# rauchmelder.net
KiCad netlist of a schematic drawn in EAGLE
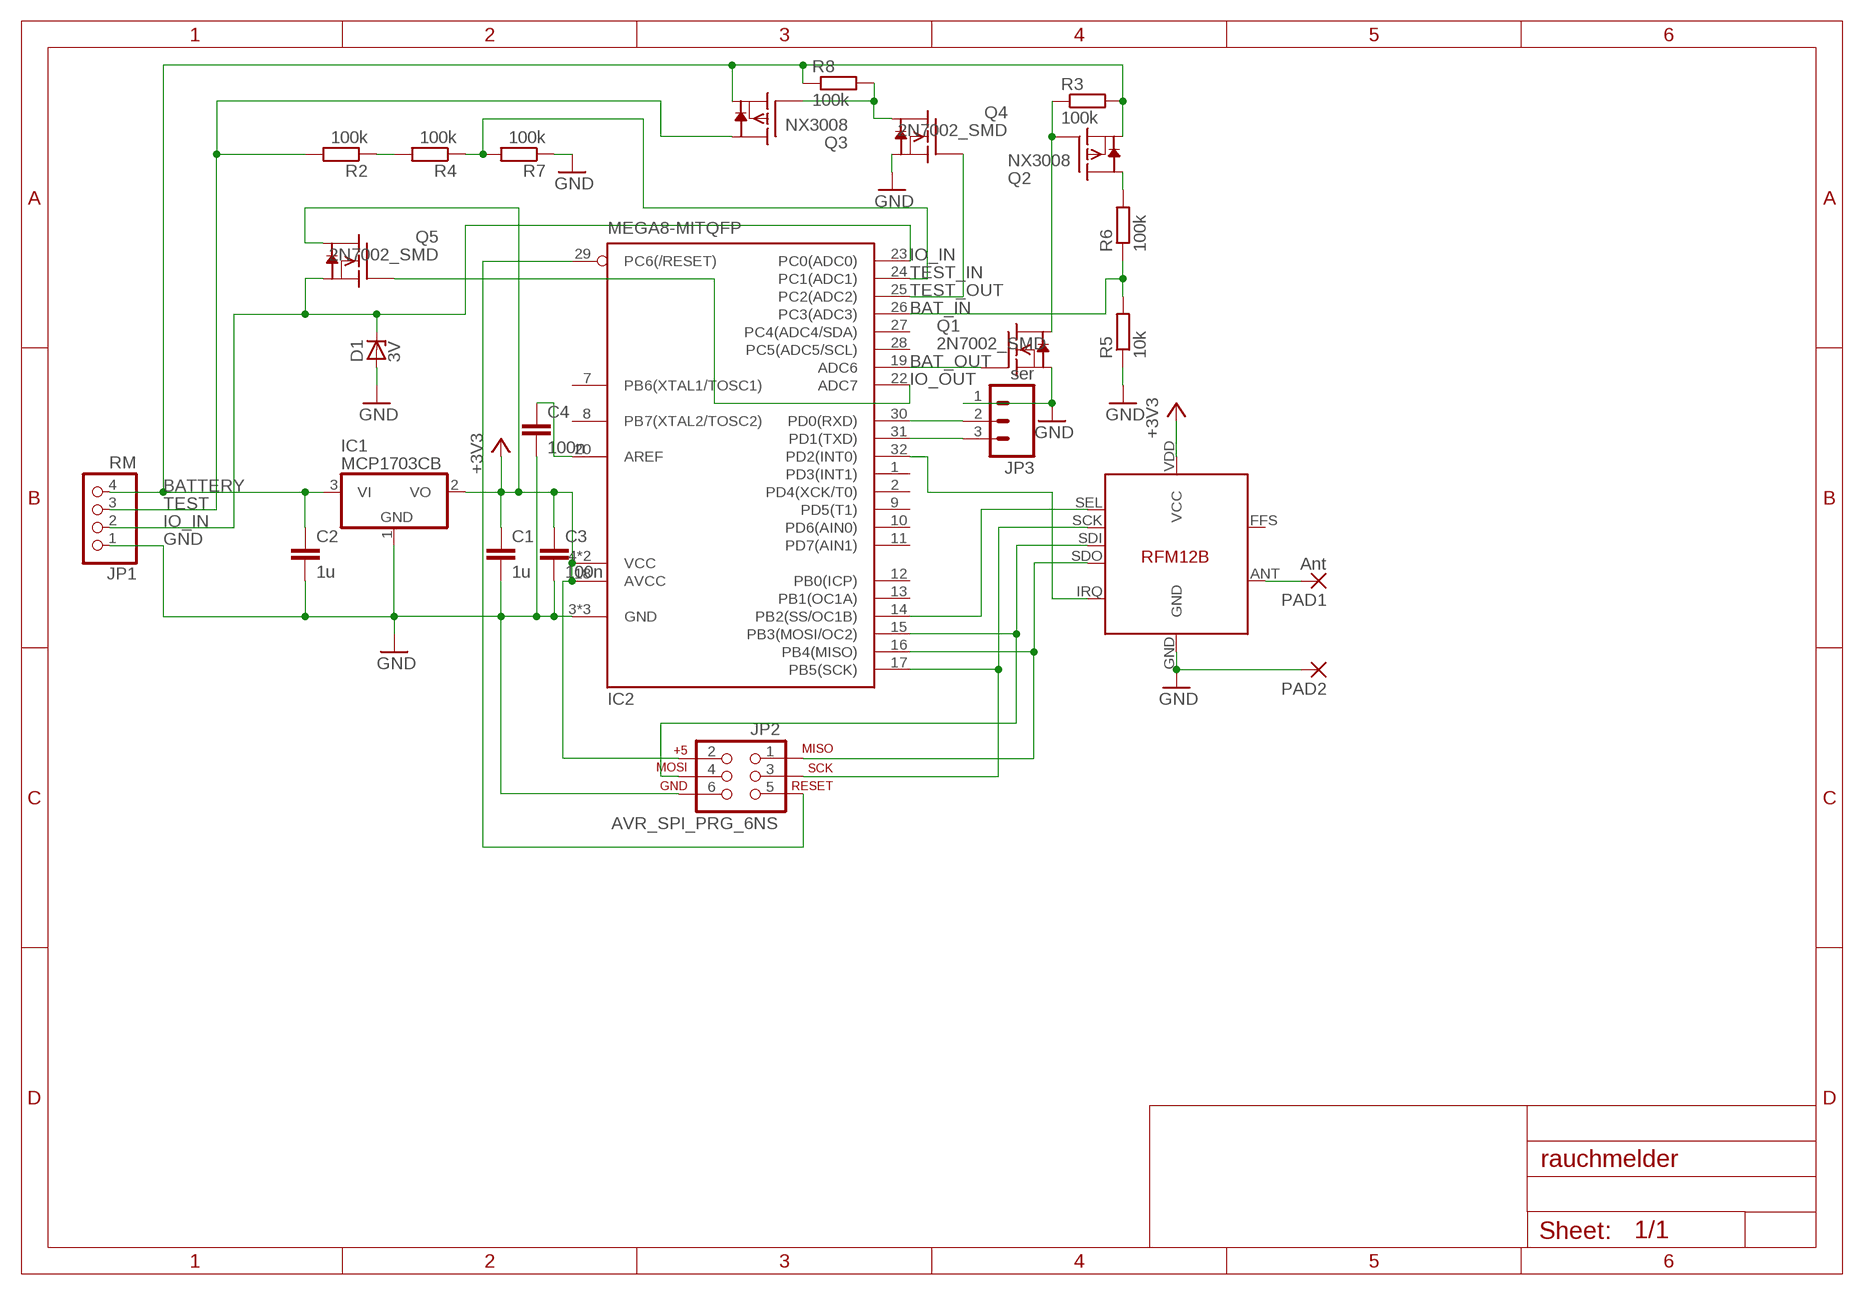
[diagram p0: schematic, sheet 1]

(export (version "E")
  (design (tool "Eeschema 10.0.6"))
  (components
    (comp (ref "C1")
      (value "1u")
      (footprint "eagle-import:C0603")
      (libsource (lib "eagle-import") (part "C-EUC0603"))
    )
    (comp (ref "C2")
      (value "1u")
      (footprint "eagle-import:C0603")
      (libsource (lib "eagle-import") (part "C-EUC0603"))
    )
    (comp (ref "C3")
      (value "100n")
      (footprint "eagle-import:C0603")
      (libsource (lib "eagle-import") (part "C-EUC0603"))
    )
    (comp (ref "C4")
      (value "100n")
      (footprint "eagle-import:C0603")
      (libsource (lib "eagle-import") (part "C-EUC0603"))
    )
    (comp (ref "D1")
      (value "3V")
      (footprint "eagle-import:SOD80C")
      (libsource (lib "eagle-import") (part "ZENER-DIODESOD80C"))
    )
    (comp (ref "IC1")
      (value "MCP1703CB")
      (footprint "eagle-import:SOT23")
      (libsource (lib "eagle-import") (part "MCP1703CB"))
    )
    (comp (ref "IC2")
      (value "MEGA8-MITQFP")
      (footprint "eagle-import:TQFP32-08")
      (libsource (lib "eagle-import") (part "MEGA8-MITQFP"))
    )
    (comp (ref "IC3")
      (value "RFM12B")
      (footprint "eagle-import:RFM12B")
      (fields (field (name "MPN") "RFM12B-868-S1"))
      (libsource (lib "eagle-import") (part "RFM12B"))
    )
    (comp (ref "JP1")
      (value "RM")
      (footprint "eagle-import:1X04")
      (libsource (lib "eagle-import") (part "PINHD-1X4"))
    )
    (comp (ref "JP2")
      (value "AVR_SPI_PRG_6NS")
      (footprint "eagle-import:2X3-NS")
      (libsource (lib "eagle-import") (part "AVR_SPI_PRG_6NS"))
    )
    (comp (ref "JP3")
      (value "ser")
      (footprint "eagle-import:1X03")
      (libsource (lib "eagle-import") (part "M03PTH"))
    )
    (comp (ref "PAD1")
      (value "Ant")
      (footprint "eagle-import:1,6_0,8")
      (libsource (lib "eagle-import") (part "1,6/0,8"))
    )
    (comp (ref "PAD2")
      (value "1,6/0,8")
      (footprint "eagle-import:1,6_0,8")
      (libsource (lib "eagle-import") (part "1,6/0,8"))
    )
    (comp (ref "Q1")
      (value "2N7002_SMD")
      (footprint "eagle-import:SOT23")
      (libsource (lib "eagle-import") (part "2N7002_SMD"))
    )
    (comp (ref "Q2")
      (value "NX3008")
      (footprint "eagle-import:SOT23")
      (fields (field (name "MPN") "NX3008NBK"))
      (libsource (lib "eagle-import") (part "NX3008"))
    )
    (comp (ref "Q3")
      (value "NX3008")
      (footprint "eagle-import:SOT23")
      (fields (field (name "MPN") "NX3008NBK"))
      (libsource (lib "eagle-import") (part "NX3008"))
    )
    (comp (ref "Q4")
      (value "2N7002_SMD")
      (footprint "eagle-import:SOT23")
      (fields (field (name "OC_FARNELL") "1829184"))
      (libsource (lib "eagle-import") (part "2N7002_SMD"))
    )
    (comp (ref "Q5")
      (value "2N7002_SMD")
      (footprint "eagle-import:SOT23")
      (fields (field (name "OC_FARNELL") "1829184"))
      (libsource (lib "eagle-import") (part "2N7002_SMD"))
    )
    (comp (ref "R2")
      (value "100k")
      (footprint "eagle-import:R0603")
      (libsource (lib "eagle-import") (part "R-EU_R0603"))
    )
    (comp (ref "R3")
      (value "100k")
      (footprint "eagle-import:R0603")
      (libsource (lib "eagle-import") (part "R-EU_R0603"))
    )
    (comp (ref "R4")
      (value "100k")
      (footprint "eagle-import:R0603")
      (libsource (lib "eagle-import") (part "R-EU_R0603"))
    )
    (comp (ref "R5")
      (value "10k")
      (footprint "eagle-import:R0603")
      (libsource (lib "eagle-import") (part "R-EU_R0603"))
    )
    (comp (ref "R6")
      (value "100k")
      (footprint "eagle-import:R0603")
      (libsource (lib "eagle-import") (part "R-EU_R0603"))
    )
    (comp (ref "R7")
      (value "100k")
      (footprint "eagle-import:R0603")
      (libsource (lib "eagle-import") (part "R-EU_R0603"))
    )
    (comp (ref "R8")
      (value "100k")
      (footprint "eagle-import:R0603")
      (libsource (lib "eagle-import") (part "R-EU_R0603"))
    )
  )
  (nets
    (net (code "1") (name "+3V3") (class "Default")
      (node (ref "C1") (pin "1") (pinfunction "1_1") (pintype "passive"))
      (node (ref "C3") (pin "1") (pinfunction "1_1") (pintype "passive"))
      (node (ref "IC1") (pin "2") (pinfunction "VO_2") (pintype "passive"))
      (node (ref "IC2") (pin "18") (pinfunction "AVCC_18") (pintype "power_in"))
      (node (ref "IC2") (pin "4") (pinfunction "VCC_4") (pintype "power_in"))
      (node (ref "IC2") (pin "6") (pinfunction "VCC_6") (pintype "power_in"))
      (node (ref "IC3") (pin "VDD") (pinfunction "VCC_VDD") (pintype "power_in"))
      (node (ref "JP2") (pin "2") (pinfunction "2_2") (pintype "passive"))
      (node (ref "Q5") (pin "3") (pinfunction "D_3") (pintype "passive"))
    )
    (net (code "2") (name "/BATTERY") (class "Default")
      (node (ref "C2") (pin "1") (pinfunction "1_1") (pintype "passive"))
      (node (ref "IC1") (pin "3") (pinfunction "VI_3") (pintype "input"))
      (node (ref "JP1") (pin "4") (pinfunction "4_4") (pintype "passive"))
      (node (ref "Q2") (pin "2") (pinfunction "S_2") (pintype "passive"))
      (node (ref "Q3") (pin "2") (pinfunction "S_2") (pintype "passive"))
      (node (ref "R3") (pin "2") (pinfunction "2_2") (pintype "passive"))
      (node (ref "R8") (pin "1") (pinfunction "1_1") (pintype "passive"))
    )
    (net (code "3") (name "/BAT_IN") (class "Default")
      (node (ref "IC2") (pin "26") (pinfunction "PC3(ADC3)_26") (pintype "bidirectional"))
      (node (ref "R5") (pin "2") (pinfunction "2_2") (pintype "passive"))
      (node (ref "R6") (pin "1") (pinfunction "1_1") (pintype "passive"))
    )
    (net (code "4") (name "/BAT_OUT") (class "Default")
      (node (ref "IC2") (pin "19") (pinfunction "ADC6_19") (pintype "bidirectional"))
      (node (ref "Q1") (pin "1") (pinfunction "G_1") (pintype "passive"))
    )
    (net (code "5") (name "/IO_IN") (class "Default")
      (node (ref "D1") (pin "C") (pinfunction "C_C") (pintype "passive"))
      (node (ref "IC2") (pin "23") (pinfunction "PC0(ADC0)_23") (pintype "bidirectional"))
      (node (ref "JP1") (pin "2") (pinfunction "2_2") (pintype "passive"))
      (node (ref "Q5") (pin "2") (pinfunction "S_2") (pintype "passive"))
    )
    (net (code "6") (name "/IO_OUT") (class "Default")
      (node (ref "IC2") (pin "22") (pinfunction "ADC7_22") (pintype "bidirectional"))
      (node (ref "Q5") (pin "1") (pinfunction "G_1") (pintype "passive"))
    )
    (net (code "7") (name "/TEST") (class "Default")
      (node (ref "JP1") (pin "3") (pinfunction "3_3") (pintype "passive"))
      (node (ref "Q3") (pin "3") (pinfunction "D_3") (pintype "passive"))
      (node (ref "R2") (pin "2") (pinfunction "2_2") (pintype "passive"))
    )
    (net (code "8") (name "/TEST_IN") (class "Default")
      (node (ref "IC2") (pin "24") (pinfunction "PC1(ADC1)_24") (pintype "bidirectional"))
      (node (ref "R4") (pin "1") (pinfunction "1_1") (pintype "passive"))
      (node (ref "R7") (pin "2") (pinfunction "2_2") (pintype "passive"))
    )
    (net (code "9") (name "/TEST_OUT") (class "Default")
      (node (ref "IC2") (pin "25") (pinfunction "PC2(ADC2)_25") (pintype "bidirectional"))
      (node (ref "Q4") (pin "1") (pinfunction "G_1") (pintype "passive"))
    )
    (net (code "10") (name "GND") (class "Default")
      (node (ref "C1") (pin "2") (pinfunction "2_2") (pintype "passive"))
      (node (ref "C2") (pin "2") (pinfunction "2_2") (pintype "passive"))
      (node (ref "C3") (pin "2") (pinfunction "2_2") (pintype "passive"))
      (node (ref "C4") (pin "2") (pinfunction "2_2") (pintype "passive"))
      (node (ref "D1") (pin "A") (pinfunction "A_A") (pintype "passive"))
      (node (ref "IC1") (pin "1") (pinfunction "GND_1") (pintype "passive"))
      (node (ref "IC2") (pin "21") (pinfunction "GND_21") (pintype "power_in"))
      (node (ref "IC2") (pin "3") (pinfunction "GND_3") (pintype "power_in"))
      (node (ref "IC2") (pin "5") (pinfunction "GND_5") (pintype "power_in"))
      (node (ref "IC3") (pin "GND") (pinfunction "GND_GND") (pintype "power_in"))
      (node (ref "JP1") (pin "1") (pinfunction "1_1") (pintype "passive"))
      (node (ref "JP2") (pin "6") (pinfunction "6_6") (pintype "passive"))
      (node (ref "JP3") (pin "1") (pinfunction "1_1") (pintype "passive"))
      (node (ref "PAD2") (pin "1") (pinfunction "P_1") (pintype "passive"))
      (node (ref "Q1") (pin "2") (pinfunction "S_2") (pintype "passive"))
      (node (ref "Q4") (pin "2") (pinfunction "S_2") (pintype "passive"))
      (node (ref "R5") (pin "1") (pinfunction "1_1") (pintype "passive"))
      (node (ref "R7") (pin "1") (pinfunction "1_1") (pintype "passive"))
    )
    (net (code "11") (name "Net-(IC2-AREF)") (class "Default")
      (node (ref "C4") (pin "1") (pinfunction "1_1") (pintype "passive"))
      (node (ref "IC2") (pin "20") (pinfunction "AREF_20") (pintype "passive"))
    )
    (net (code "12") (name "Net-(IC2-PB2(SS{slash}OC1B))") (class "Default")
      (node (ref "IC2") (pin "14") (pinfunction "PB2(SS/OC1B)_14") (pintype "bidirectional"))
      (node (ref "IC3") (pin "SEL") (pinfunction "SEL_SEL") (pintype "input"))
    )
    (net (code "13") (name "Net-(IC2-PB3(MOSI{slash}OC2))") (class "Default")
      (node (ref "IC2") (pin "15") (pinfunction "PB3(MOSI/OC2)_15") (pintype "bidirectional"))
      (node (ref "IC3") (pin "SDI") (pinfunction "SDI_SDI") (pintype "input"))
      (node (ref "JP2") (pin "4") (pinfunction "4_4") (pintype "passive"))
    )
    (net (code "14") (name "Net-(IC2-PB4(MISO))") (class "Default")
      (node (ref "IC2") (pin "16") (pinfunction "PB4(MISO)_16") (pintype "bidirectional"))
      (node (ref "IC3") (pin "SDO") (pinfunction "SDO_SDO") (pintype "output"))
      (node (ref "JP2") (pin "1") (pinfunction "1_1") (pintype "passive"))
    )
    (net (code "15") (name "Net-(IC2-PB5(SCK))") (class "Default")
      (node (ref "IC2") (pin "17") (pinfunction "PB5(SCK)_17") (pintype "bidirectional"))
      (node (ref "IC3") (pin "SCK") (pinfunction "SCK_SCK") (pintype "input"))
      (node (ref "JP2") (pin "3") (pinfunction "3_3") (pintype "passive"))
    )
    (net (code "16") (name "Net-(IC2-PC6({slash}RESET))") (class "Default")
      (node (ref "IC2") (pin "29") (pinfunction "PC6(/RESET)_29") (pintype "bidirectional"))
      (node (ref "JP2") (pin "5") (pinfunction "5_5") (pintype "passive"))
    )
    (net (code "17") (name "Net-(IC2-PD0(RXD))") (class "Default")
      (node (ref "IC2") (pin "30") (pinfunction "PD0(RXD)_30") (pintype "bidirectional"))
      (node (ref "JP3") (pin "2") (pinfunction "2_2") (pintype "passive"))
    )
    (net (code "18") (name "Net-(IC2-PD1(TXD))") (class "Default")
      (node (ref "IC2") (pin "31") (pinfunction "PD1(TXD)_31") (pintype "bidirectional"))
      (node (ref "JP3") (pin "3") (pinfunction "3_3") (pintype "passive"))
    )
    (net (code "19") (name "Net-(IC2-PD2(INT0))") (class "Default")
      (node (ref "IC2") (pin "32") (pinfunction "PD2(INT0)_32") (pintype "bidirectional"))
      (node (ref "IC3") (pin "IRQ") (pinfunction "IRQ_IRQ") (pintype "open_collector"))
    )
    (net (code "20") (name "Net-(PAD1-P)") (class "Default")
      (node (ref "IC3") (pin "ANT") (pinfunction "ANT_ANT") (pintype "passive"))
      (node (ref "PAD1") (pin "1") (pinfunction "P_1") (pintype "passive"))
    )
    (net (code "21") (name "Net-(Q1-D)") (class "Default")
      (node (ref "Q1") (pin "3") (pinfunction "D_3") (pintype "passive"))
      (node (ref "Q2") (pin "1") (pinfunction "G_1") (pintype "passive"))
      (node (ref "R3") (pin "1") (pinfunction "1_1") (pintype "passive"))
    )
    (net (code "22") (name "Net-(Q2-D)") (class "Default")
      (node (ref "Q2") (pin "3") (pinfunction "D_3") (pintype "passive"))
      (node (ref "R6") (pin "2") (pinfunction "2_2") (pintype "passive"))
    )
    (net (code "23") (name "Net-(Q3-G)") (class "Default")
      (node (ref "Q3") (pin "1") (pinfunction "G_1") (pintype "passive"))
      (node (ref "Q4") (pin "3") (pinfunction "D_3") (pintype "passive"))
      (node (ref "R8") (pin "2") (pinfunction "2_2") (pintype "passive"))
    )
    (net (code "24") (name "Net-(R2-Pad1)") (class "Default")
      (node (ref "R2") (pin "1") (pinfunction "1_1") (pintype "passive"))
      (node (ref "R4") (pin "2") (pinfunction "2_2") (pintype "passive"))
    )
    (net (code "25") (name "unconnected-(IC2-PB0(ICP)-Pad12)") (class "Default")
      (node (ref "IC2") (pin "12") (pinfunction "PB0(ICP)_12") (pintype "bidirectional"))
    )
    (net (code "26") (name "unconnected-(IC2-PB1(OC1A)-Pad13)") (class "Default")
      (node (ref "IC2") (pin "13") (pinfunction "PB1(OC1A)_13") (pintype "bidirectional"))
    )
    (net (code "27") (name "unconnected-(IC2-PB6(XTAL1{slash}TOSC1)-Pad7)") (class "Default")
      (node (ref "IC2") (pin "7") (pinfunction "PB6(XTAL1/TOSC1)_7") (pintype "bidirectional"))
    )
    (net (code "28") (name "unconnected-(IC2-PB7(XTAL2{slash}TOSC2)-Pad8)") (class "Default")
      (node (ref "IC2") (pin "8") (pinfunction "PB7(XTAL2/TOSC2)_8") (pintype "bidirectional"))
    )
    (net (code "29") (name "unconnected-(IC2-PC4(ADC4{slash}SDA)-Pad27)") (class "Default")
      (node (ref "IC2") (pin "27") (pinfunction "PC4(ADC4/SDA)_27") (pintype "bidirectional"))
    )
    (net (code "30") (name "unconnected-(IC2-PC5(ADC5{slash}SCL)-Pad28)") (class "Default")
      (node (ref "IC2") (pin "28") (pinfunction "PC5(ADC5/SCL)_28") (pintype "bidirectional"))
    )
    (net (code "31") (name "unconnected-(IC2-PD3(INT1)-Pad1)") (class "Default")
      (node (ref "IC2") (pin "1") (pinfunction "PD3(INT1)_1") (pintype "bidirectional"))
    )
    (net (code "32") (name "unconnected-(IC2-PD4(XCK{slash}T0)-Pad2)") (class "Default")
      (node (ref "IC2") (pin "2") (pinfunction "PD4(XCK/T0)_2") (pintype "bidirectional"))
    )
    (net (code "33") (name "unconnected-(IC2-PD5(T1)-Pad9)") (class "Default")
      (node (ref "IC2") (pin "9") (pinfunction "PD5(T1)_9") (pintype "bidirectional"))
    )
    (net (code "34") (name "unconnected-(IC2-PD6(AIN0)-Pad10)") (class "Default")
      (node (ref "IC2") (pin "10") (pinfunction "PD6(AIN0)_10") (pintype "bidirectional"))
    )
    (net (code "35") (name "unconnected-(IC2-PD7(AIN1)-Pad11)") (class "Default")
      (node (ref "IC2") (pin "11") (pinfunction "PD7(AIN1)_11") (pintype "bidirectional"))
    )
    (net (code "36") (name "unconnected-(IC3-PadFFS)") (class "Default")
      (node (ref "IC3") (pin "FFS") (pinfunction "FFS_FFS") (pintype "bidirectional"))
    )
  )
)
